# motor_comp.net
KiCad netlist of a schematic drawn in EAGLE
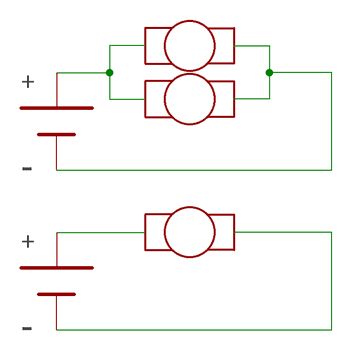
[diagram p0: schematic, sheet 1]

(export (version "E")
  (design (tool "Eeschema 10.0.6"))
  (components
    (comp (ref "U$1")
      (value "MABUCHI-FC280SA")
      (footprint "eagle-import:DC_MOTOR")
      (libsource (lib "eagle-import") (part "MABUCHI-FC280SA"))
    )
    (comp (ref "U$2")
      (value "MABUCHI-FC280SA")
      (footprint "eagle-import:DC_MOTOR")
      (libsource (lib "eagle-import") (part "MABUCHI-FC280SA"))
    )
    (comp (ref "U$3")
      (value "BATTERY")
      (footprint "eagle-import:DC_MOTOR")
      (libsource (lib "eagle-import") (part "BATTERY"))
    )
    (comp (ref "U$5")
      (value "MABUCHI-FC280SA")
      (footprint "eagle-import:DC_MOTOR")
      (libsource (lib "eagle-import") (part "MABUCHI-FC280SA"))
    )
    (comp (ref "U$6")
      (value "BATTERY")
      (footprint "eagle-import:DC_MOTOR")
      (libsource (lib "eagle-import") (part "BATTERY"))
    )
  )
  (nets
    (net (code "1") (name "Net-(U$1-PadP$1)") (class "Default")
      (node (ref "U$1") (pin "P$1") (pinfunction "P$1_P$1") (pintype "bidirectional"))
      (node (ref "U$2") (pin "P$1") (pinfunction "P$1_P$1") (pintype "bidirectional"))
      (node (ref "U$3") (pin "P$1") (pinfunction "P$1_P$1") (pintype "bidirectional"))
    )
    (net (code "2") (name "Net-(U$1-PadP$2)") (class "Default")
      (node (ref "U$1") (pin "P$2") (pinfunction "P$2_P$2") (pintype "bidirectional"))
      (node (ref "U$2") (pin "P$2") (pinfunction "P$2_P$2") (pintype "bidirectional"))
      (node (ref "U$3") (pin "P$2") (pinfunction "P$2_P$2") (pintype "bidirectional"))
    )
    (net (code "3") (name "Net-(U$5-PadP$1)") (class "Default")
      (node (ref "U$5") (pin "P$1") (pinfunction "P$1_P$1") (pintype "bidirectional"))
      (node (ref "U$6") (pin "P$1") (pinfunction "P$1_P$1") (pintype "bidirectional"))
    )
    (net (code "4") (name "Net-(U$5-PadP$2)") (class "Default")
      (node (ref "U$5") (pin "P$2") (pinfunction "P$2_P$2") (pintype "bidirectional"))
      (node (ref "U$6") (pin "P$2") (pinfunction "P$2_P$2") (pintype "bidirectional"))
    )
  )
)
